# efuse.net
KiCad netlist of a schematic drawn in EAGLE
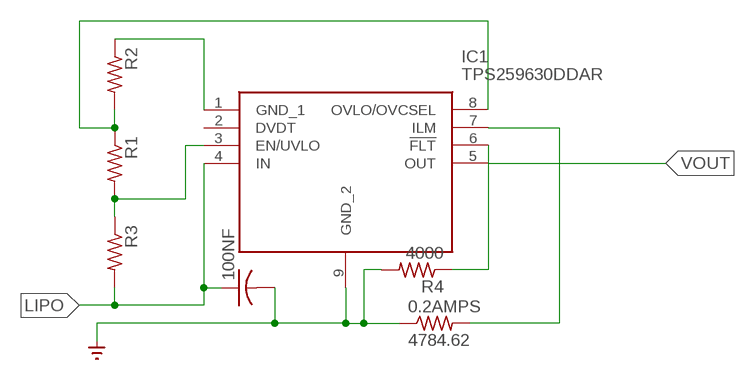
[diagram p0: schematic, sheet 1]

(export (version "E")
  (design (tool "Eeschema 10.0.6"))
  (components
    (comp (ref "0.2AMPS")
      (value "4784.62")
      (footprint "eagle-import:M0805")
      (libsource (lib "eagle-import") (part "R-US_M0805"))
    )
    (comp (ref "100NF")
      (value "C-USC0805")
      (footprint "eagle-import:C0805")
      (libsource (lib "eagle-import") (part "C-USC0805"))
    )
    (comp (ref "IC1")
      (value "TPS259630DDAR")
      (footprint "eagle-import:SOIC127P600X170-9N")
      (fields (field (name "MOUSER_PART_NUMBER") "595-TPS259630DDAR"))
      (libsource (lib "eagle-import") (part "TPS259630DDAR"))
    )
    (comp (ref "R1")
      (value "R-US_M0805")
      (footprint "eagle-import:M0805")
      (libsource (lib "eagle-import") (part "R-US_M0805"))
    )
    (comp (ref "R2")
      (value "R-US_M0805")
      (footprint "eagle-import:M0805")
      (libsource (lib "eagle-import") (part "R-US_M0805"))
    )
    (comp (ref "R3")
      (value "R-US_M0805")
      (footprint "eagle-import:M0805")
      (libsource (lib "eagle-import") (part "R-US_M0805"))
    )
    (comp (ref "R4")
      (value "4000")
      (footprint "eagle-import:R0805")
      (libsource (lib "eagle-import") (part "R-US_R0805"))
    )
  )
  (nets
    (net (code "1") (name "LIPO") (class "Default")
      (node (ref "100NF") (pin "1") (pinfunction "1_1") (pintype "passive"))
      (node (ref "IC1") (pin "4") (pinfunction "IN_4") (pintype "bidirectional"))
      (node (ref "R3") (pin "2") (pinfunction "2_2") (pintype "passive"))
    )
    (net (code "2") (name "Net-(IC1-EN{slash}UVLO)") (class "Default")
      (node (ref "IC1") (pin "3") (pinfunction "EN/UVLO_3") (pintype "bidirectional"))
      (node (ref "R1") (pin "2") (pinfunction "2_2") (pintype "passive"))
      (node (ref "R3") (pin "1") (pinfunction "1_1") (pintype "passive"))
    )
    (net (code "3") (name "Net-(IC1-GND_1)") (class "Default")
      (node (ref "IC1") (pin "1") (pinfunction "GND_1_1") (pintype "bidirectional"))
      (node (ref "R2") (pin "1") (pinfunction "1_1") (pintype "passive"))
    )
    (net (code "4") (name "Net-(IC1-ILM)") (class "Default")
      (node (ref "0.2AMPS") (pin "2") (pinfunction "2_2") (pintype "passive"))
      (node (ref "IC1") (pin "7") (pinfunction "ILM_7") (pintype "bidirectional"))
    )
    (net (code "5") (name "Net-(IC1-OVLO{slash}OVCSEL)") (class "Default")
      (node (ref "IC1") (pin "8") (pinfunction "OVLO/OVCSEL_8") (pintype "bidirectional"))
      (node (ref "R1") (pin "1") (pinfunction "1_1") (pintype "passive"))
      (node (ref "R2") (pin "2") (pinfunction "2_2") (pintype "passive"))
    )
    (net (code "6") (name "Net-(IC1-~{FLT})") (class "Default")
      (node (ref "IC1") (pin "6") (pinfunction "~{FLT}_6") (pintype "bidirectional"))
      (node (ref "R4") (pin "1") (pinfunction "1_1") (pintype "passive"))
    )
    (net (code "7") (name "SUPPLY0_GND_") (class "Default")
      (node (ref "0.2AMPS") (pin "1") (pinfunction "1_1") (pintype "passive"))
      (node (ref "100NF") (pin "2") (pinfunction "2_2") (pintype "passive"))
      (node (ref "IC1") (pin "9") (pinfunction "GND_2_9") (pintype "bidirectional"))
      (node (ref "R4") (pin "2") (pinfunction "2_2") (pintype "passive"))
    )
    (net (code "8") (name "VOUT") (class "Default")
      (node (ref "IC1") (pin "5") (pinfunction "OUT_5") (pintype "bidirectional"))
    )
    (net (code "9") (name "unconnected-(IC1-DVDT-Pad2)") (class "Default")
      (node (ref "IC1") (pin "2") (pinfunction "DVDT_2") (pintype "bidirectional"))
    )
  )
)
